# driver-ha-v4-rev1.net
KiCad netlist of a schematic drawn in EAGLE
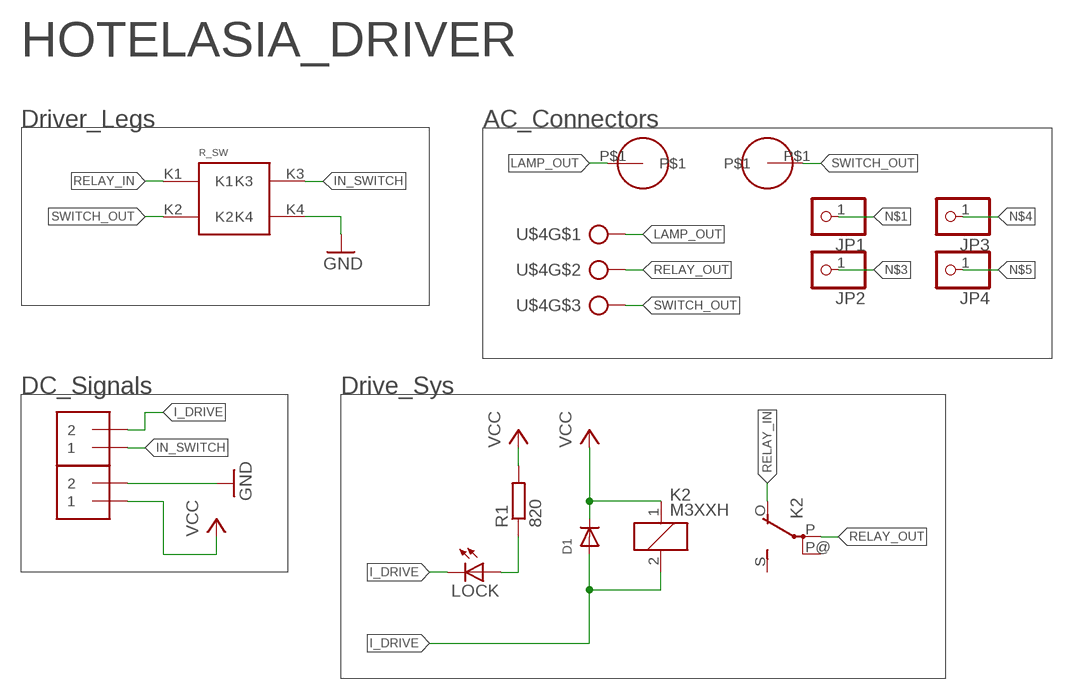
[diagram p0: schematic, sheet 1]

(export (version "E")
  (design (tool "Eeschema 10.0.6"))
  (components
    (comp (ref "D1")
      (value "DIODESMA")
      (footprint "eagle-import:SMADIODE")
      (libsource (lib "eagle-import") (part "DIODESMA"))
    )
    (comp (ref "J1")
      (value "1X2-3.5MM")
      (footprint "eagle-import:1X2-3.5MM")
      (libsource (lib "eagle-import") (part "1X2-3.5MM"))
    )
    (comp (ref "J2")
      (value "1X2-3.5MM")
      (footprint "eagle-import:1X2-3.5MM")
      (libsource (lib "eagle-import") (part "1X2-3.5MM"))
    )
    (comp (ref "JP1")
      (value "PINHD-1X1")
      (footprint "eagle-import:1X01")
      (libsource (lib "eagle-import") (part "PINHD-1X1"))
    )
    (comp (ref "JP2")
      (value "PINHD-1X1")
      (footprint "eagle-import:1X01")
      (libsource (lib "eagle-import") (part "PINHD-1X1"))
    )
    (comp (ref "JP3")
      (value "PINHD-1X1")
      (footprint "eagle-import:1X01")
      (libsource (lib "eagle-import") (part "PINHD-1X1"))
    )
    (comp (ref "JP4")
      (value "PINHD-1X1")
      (footprint "eagle-import:1X01")
      (libsource (lib "eagle-import") (part "PINHD-1X1"))
    )
    (comp (ref "K2")
      (value "M3XXH")
      (footprint "eagle-import:M3XXH")
      (libsource (lib "eagle-import") (part "M3XXH"))
    )
    (comp (ref "LOCK")
      (value "LED3MM")
      (footprint "eagle-import:LED3MM")
      (libsource (lib "eagle-import") (part "LED3MM"))
    )
    (comp (ref "PAD1")
      (value "ROOM_SWITCH")
      (footprint "eagle-import:ROOM_SWITCH")
      (libsource (lib "eagle-import") (part "ROOM_SWITCH"))
    )
    (comp (ref "R1")
      (value "820")
      (footprint "eagle-import:R0805")
      (libsource (lib "eagle-import") (part "R-EU_R0805"))
    )
    (comp (ref "U$1")
      (value "CONN-CABLE")
      (footprint "eagle-import:CONN-CABLE")
      (libsource (lib "eagle-import") (part "CONN-CABLE"))
    )
    (comp (ref "U$3")
      (value "CONN-CABLE")
      (footprint "eagle-import:CONN-CABLE")
      (libsource (lib "eagle-import") (part "CONN-CABLE"))
    )
    (comp (ref "U$4")
      (value "AK3003")
      (footprint "eagle-import:AK3003")
      (libsource (lib "eagle-import") (part "AK3003"))
    )
  )
  (nets
    (net (code "1") (name "GND") (class "Default")
      (node (ref "J2") (pin "2") (pinfunction "2_2") (pintype "passive"))
      (node (ref "PAD1") (pin "K4") (pinfunction "K4_K4") (pintype "bidirectional"))
    )
    (net (code "2") (name "IN_SWITCH") (class "Default")
      (node (ref "J1") (pin "1") (pinfunction "1_1") (pintype "passive"))
      (node (ref "PAD1") (pin "K3") (pinfunction "K3_K3") (pintype "bidirectional"))
    )
    (net (code "3") (name "I_DRIVE") (class "Default")
      (node (ref "D1") (pin "A") (pinfunction "A_A") (pintype "passive"))
      (node (ref "J1") (pin "2") (pinfunction "2_2") (pintype "passive"))
      (node (ref "K2") (pin "2") (pinfunction "2_2") (pintype "passive"))
      (node (ref "LOCK") (pin "K") (pinfunction "C_K") (pintype "passive"))
    )
    (net (code "4") (name "LAMP_OUT") (class "Default")
      (node (ref "U$1") (pin "P$1") (pinfunction "P$1_P$1") (pintype "bidirectional"))
      (node (ref "U$4") (pin "1") (pinfunction "KL_1") (pintype "passive"))
    )
    (net (code "5") (name "N$1") (class "Default")
      (node (ref "JP1") (pin "1") (pinfunction "1_1") (pintype "passive"))
    )
    (net (code "6") (name "N$3") (class "Default")
      (node (ref "JP2") (pin "1") (pinfunction "1_1") (pintype "passive"))
    )
    (net (code "7") (name "N$4") (class "Default")
      (node (ref "JP3") (pin "1") (pinfunction "1_1") (pintype "passive"))
    )
    (net (code "8") (name "N$5") (class "Default")
      (node (ref "JP4") (pin "1") (pinfunction "1_1") (pintype "passive"))
    )
    (net (code "9") (name "Net-(LOCK-PadA)") (class "Default")
      (node (ref "LOCK") (pin "A") (pinfunction "A_A") (pintype "passive"))
      (node (ref "R1") (pin "1") (pinfunction "1_1") (pintype "passive"))
    )
    (net (code "10") (name "RELAY_IN") (class "Default")
      (node (ref "K2") (pin "O") (pinfunction "O_O") (pintype "passive"))
      (node (ref "PAD1") (pin "K1") (pinfunction "K1_K1") (pintype "bidirectional"))
    )
    (net (code "11") (name "RELAY_OUT") (class "Default")
      (node (ref "K2") (pin "P") (pinfunction "P_P") (pintype "passive"))
      (node (ref "U$4") (pin "2") (pinfunction "KL_2") (pintype "passive"))
    )
    (net (code "12") (name "SWITCH_OUT") (class "Default")
      (node (ref "PAD1") (pin "K2") (pinfunction "K2_K2") (pintype "bidirectional"))
      (node (ref "U$3") (pin "P$1") (pinfunction "P$1_P$1") (pintype "bidirectional"))
      (node (ref "U$4") (pin "3") (pinfunction "KL_3") (pintype "passive"))
    )
    (net (code "13") (name "VCC") (class "Default")
      (node (ref "D1") (pin "C") (pinfunction "C_C") (pintype "passive"))
      (node (ref "J2") (pin "1") (pinfunction "1_1") (pintype "passive"))
      (node (ref "K2") (pin "1") (pinfunction "1_1") (pintype "passive"))
      (node (ref "R1") (pin "2") (pinfunction "2_2") (pintype "passive"))
    )
    (net (code "14") (name "unconnected-(K2-PadS)") (class "Default")
      (node (ref "K2") (pin "S") (pinfunction "S_S") (pintype "passive"))
    )
    (net (code "15") (name "unconnected-(K2B-P-PadP@)") (class "Default")
      (node (ref "K2") (pin "P@") (pinfunction "P_P@") (pintype "passive"))
    )
  )
)
